# DE-180417_03.net
KiCad netlist of a schematic drawn in Altium Designer
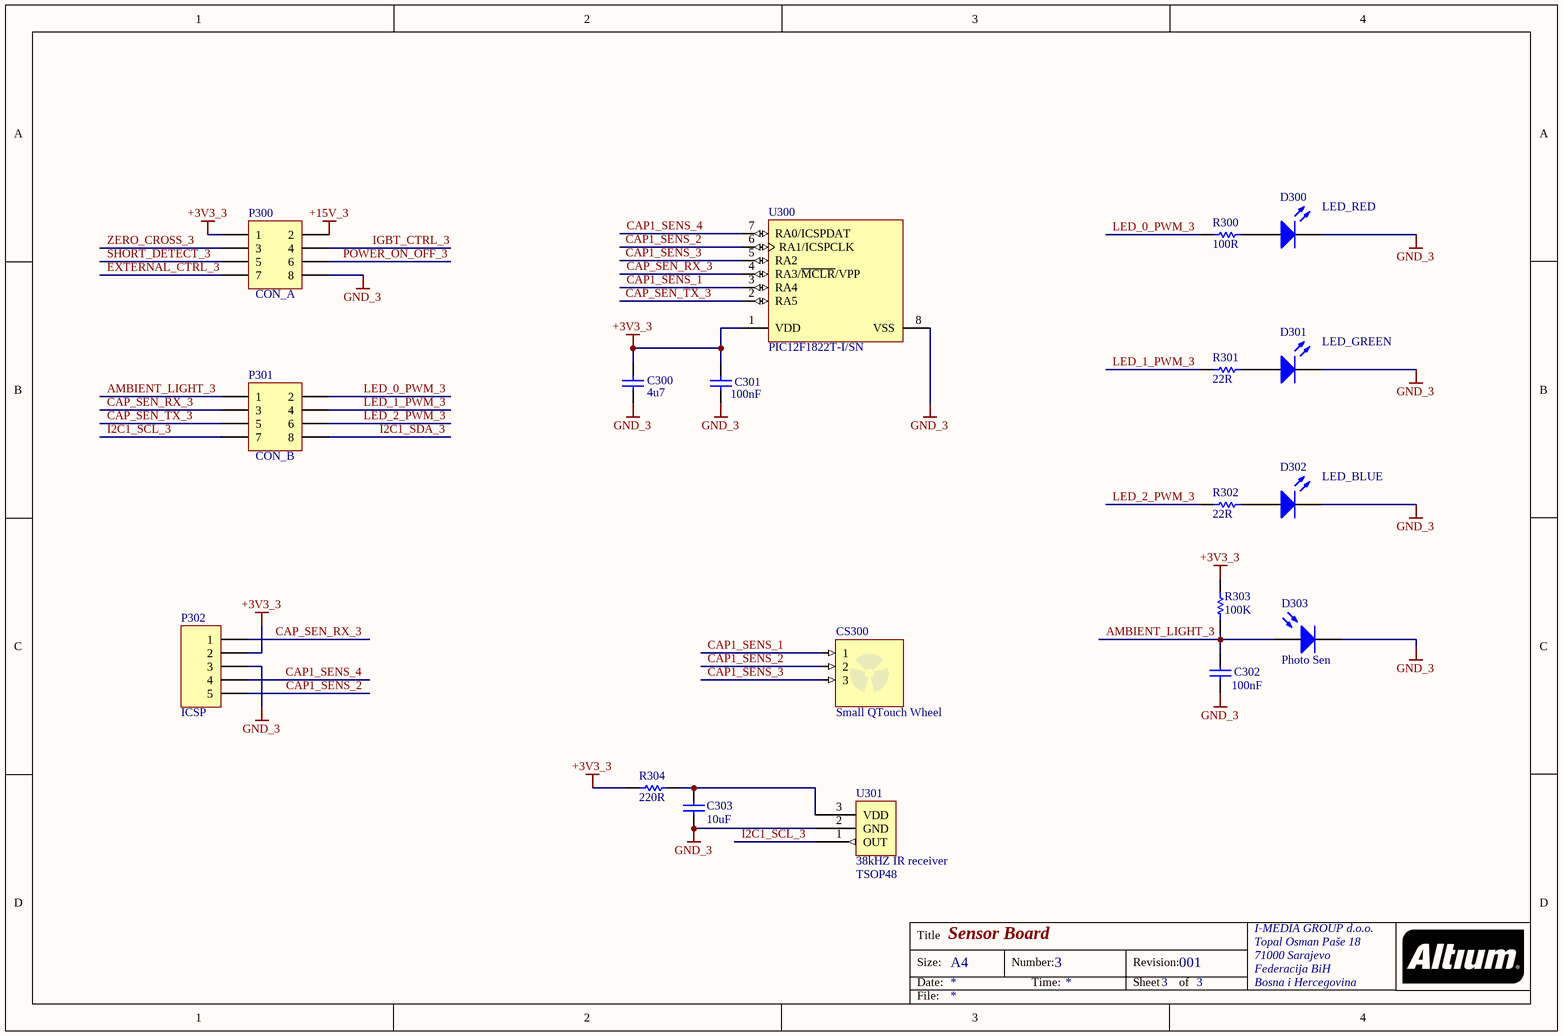
[diagram p0: DE-180417_03.SchDoc]

(export (version "E")
  (design (tool "Eeschema 10.0.6"))
  (components
    (comp (ref "C300")
      (value "4u7")
      (footprint "0805")
      (description "Ceramic Chip Capacitor - Standard")
      (fields (field (name "PUBLISHER") "Altium Limited"))
      (libsource (lib "KEMET Chip Capacitor") (part "C0805"))
    )
    (comp (ref "C301")
      (value "100nF")
      (footprint "0603")
      (description "Ceramic Chip Capacitor - Standard")
      (fields (field (name "PUBLISHER") "Altium Limited"))
      (libsource (lib "KEMET Chip Capacitor") (part "C0603"))
    )
    (comp (ref "C302")
      (value "100nF")
      (footprint "0603")
      (description "Ceramic Chip Capacitor - Standard")
      (fields (field (name "PUBLISHER") "Altium Limited"))
      (libsource (lib "KEMET Chip Capacitor") (part "C0603"))
    )
    (comp (ref "C303")
      (value "10uF")
      (footprint "0805")
      (description "Ceramic Chip Capacitor - Standard")
      (fields (field (name "PUBLISHER") "Altium Limited"))
      (libsource (lib "DE-180417") (part "C0805"))
    )
    (comp (ref "CS300")
      (value "Small QTouch Wheel")
      (libsource (lib "Atmel QTouch") (part "SmallQTouchWheel"))
    )
    (comp (ref "D300")
      (value "LED_RED")
      (footprint "1.6X0.8X0.8")
      (description "High Performance Chip LED, Red")
      (fields (field (name "PUBLISHER") "Altium Limited"))
      (libsource (lib "DE-180417") (part "HSMZ-C190"))
    )
    (comp (ref "D301")
      (value "LED_GREEN")
      (footprint "1.6X0.8X0.8")
      (description "High Performance Chip LED, Red")
      (fields (field (name "PUBLISHER") "Altium Limited"))
      (libsource (lib "DE-180417") (part "HSMZ-C190"))
    )
    (comp (ref "D302")
      (value "LED_BLUE")
      (footprint "1.6X0.8X0.8")
      (description "High Performance Chip LED, Red")
      (fields (field (name "PUBLISHER") "Altium Limited"))
      (libsource (lib "DE-180417") (part "HSMZ-C190"))
    )
    (comp (ref "D303")
      (value "Photo Sen")
      (footprint "PIN2")
      (description "Photosensitive Diode")
      (fields (field (name "PUBLISHER") "Altium Limited"))
      (libsource (lib "Miscellaneous Devices") (part "Photo Sen"))
    )
    (comp (ref "P300")
      (value "CON_A")
      (footprint "HDR2X4")
      (description "Header, 4-Pin, Dual row")
      (fields (field (name "PUBLISHER") "Altium Limited"))
      (libsource (lib "Miscellaneous Connectors") (part "Header 4X2"))
    )
    (comp (ref "P301")
      (value "CON_B")
      (footprint "HDR2X4")
      (description "Header, 4-Pin, Dual row")
      (fields (field (name "PUBLISHER") "Altium Limited"))
      (libsource (lib "Miscellaneous Connectors") (part "Header 4X2"))
    )
    (comp (ref "P302")
      (value "ICSP")
      (footprint "HDR1X5")
      (description "Header, 5-Pin")
      (fields (field (name "PUBLISHER") "Altium Limited"))
      (libsource (lib "Miscellaneous Connectors") (part "Header 5"))
    )
    (comp (ref "R300")
      (value "100R")
      (footprint "ERA-0603")
      (fields (field (name "PUBLISHER") "Altium Limited"))
      (libsource (lib "DE-180417") (part "ERAV"))
    )
    (comp (ref "R301")
      (value "22R")
      (footprint "ERA-0603")
      (fields (field (name "PUBLISHER") "Altium Limited"))
      (libsource (lib "DE-180417") (part "ERAV"))
    )
    (comp (ref "R302")
      (value "22R")
      (footprint "ERA-0603")
      (fields (field (name "PUBLISHER") "Altium Limited"))
      (libsource (lib "DE-180417") (part "ERAV"))
    )
    (comp (ref "R303")
      (value "100K")
      (footprint "ERA-0603")
      (fields (field (name "PUBLISHER") "Altium Limited"))
      (libsource (lib "DE-180417") (part "ERAV"))
    )
    (comp (ref "R304")
      (value "220R")
      (footprint "ERA-0603")
      (fields (field (name "PUBLISHER") "Altium Limited"))
      (libsource (lib "DE-180417") (part "ERAV"))
    )
    (comp (ref "U300")
      (value "PIC12F1822T-I/SN")
      (footprint "MCHP-SOIC-SN8_N")
      (fields (field (name "MANUFACTURER") "Microchip"))
      (libsource (lib "Microchip PIC12") (part "PIC12F1822T-I/SN"))
    )
    (comp (ref "U301")
      (value "38kHZ IR receiver")
      (footprint "TSOP48")
      (fields (field (name "ALTIUM_VALUE") "TSOP48"))
      (libsource (lib "DE-180417") (part "TSOP48"))
    )
  )
  (nets
    (net (code "1") (name "+3V3_3") (class "Default")
      (node (ref "C300") (pin "1") (pinfunction "1_1") (pintype "passive"))
      (node (ref "C301") (pin "1") (pinfunction "1_1") (pintype "passive"))
      (node (ref "P300") (pin "1") (pinfunction "1_1") (pintype "passive"))
      (node (ref "P302") (pin "2") (pinfunction "2_2") (pintype "passive"))
      (node (ref "R303") (pin "1") (pinfunction "1_1") (pintype "passive"))
      (node (ref "R304") (pin "1") (pinfunction "1_1") (pintype "passive"))
      (node (ref "U300") (pin "1") (pinfunction "VDD_1") (pintype "power_in"))
    )
    (net (code "2") (name "+15V_3") (class "Default")
      (node (ref "P300") (pin "2") (pinfunction "2_2") (pintype "passive"))
    )
    (net (code "3") (name "/AMBIENT_LIGHT_3") (class "Default")
      (node (ref "C302") (pin "1") (pinfunction "1_1") (pintype "passive"))
      (node (ref "D303") (pin "1") (pinfunction "A_1") (pintype "passive"))
      (node (ref "P301") (pin "1") (pinfunction "1_1") (pintype "passive"))
      (node (ref "R303") (pin "2") (pinfunction "2_2") (pintype "passive"))
    )
    (net (code "4") (name "/CAP1_SENS_1") (class "Default")
      (node (ref "CS300") (pin "1") (pinfunction "1_1") (pintype "input"))
      (node (ref "U300") (pin "3") (pinfunction "RA4_3") (pintype "bidirectional"))
    )
    (net (code "5") (name "/CAP1_SENS_2") (class "Default")
      (node (ref "CS300") (pin "2") (pinfunction "2_2") (pintype "input"))
      (node (ref "P302") (pin "5") (pinfunction "5_5") (pintype "passive"))
      (node (ref "U300") (pin "6") (pinfunction "RA1/ICSPCLK_6") (pintype "bidirectional"))
    )
    (net (code "6") (name "/CAP1_SENS_3") (class "Default")
      (node (ref "CS300") (pin "3") (pinfunction "3_3") (pintype "input"))
      (node (ref "U300") (pin "5") (pinfunction "RA2_5") (pintype "bidirectional"))
    )
    (net (code "7") (name "/CAP1_SENS_4") (class "Default")
      (node (ref "P302") (pin "4") (pinfunction "4_4") (pintype "passive"))
      (node (ref "U300") (pin "7") (pinfunction "RA0/ICSPDAT_7") (pintype "bidirectional"))
    )
    (net (code "8") (name "/CAP_SEN_RX_3") (class "Default")
      (node (ref "P301") (pin "3") (pinfunction "3_3") (pintype "passive"))
      (node (ref "P302") (pin "1") (pinfunction "1_1") (pintype "passive"))
      (node (ref "U300") (pin "4") (pinfunction "RA3/~{MCLR}/VPP_4") (pintype "bidirectional"))
    )
    (net (code "9") (name "/CAP_SEN_TX_3") (class "Default")
      (node (ref "P301") (pin "5") (pinfunction "5_5") (pintype "passive"))
      (node (ref "U300") (pin "2") (pinfunction "RA5_2") (pintype "bidirectional"))
    )
    (net (code "10") (name "/EXTERNAL_CTRL_3") (class "Default")
      (node (ref "P300") (pin "7") (pinfunction "7_7") (pintype "passive"))
    )
    (net (code "11") (name "/I2C1_SCL_3") (class "Default")
      (node (ref "P301") (pin "7") (pinfunction "7_7") (pintype "passive"))
      (node (ref "U301") (pin "1") (pinfunction "OUT_1") (pintype "output"))
    )
    (net (code "12") (name "/I2C1_SDA_3") (class "Default")
      (node (ref "P301") (pin "8") (pinfunction "8_8") (pintype "passive"))
    )
    (net (code "13") (name "/IGBT_CTRL_3") (class "Default")
      (node (ref "P300") (pin "4") (pinfunction "4_4") (pintype "passive"))
    )
    (net (code "14") (name "/LED_0_PWM_3") (class "Default")
      (node (ref "P301") (pin "2") (pinfunction "2_2") (pintype "passive"))
      (node (ref "R300") (pin "2") (pinfunction "2_2") (pintype "passive"))
    )
    (net (code "15") (name "/LED_1_PWM_3") (class "Default")
      (node (ref "P301") (pin "4") (pinfunction "4_4") (pintype "passive"))
      (node (ref "R301") (pin "2") (pinfunction "2_2") (pintype "passive"))
    )
    (net (code "16") (name "/LED_2_PWM_3") (class "Default")
      (node (ref "P301") (pin "6") (pinfunction "6_6") (pintype "passive"))
      (node (ref "R302") (pin "2") (pinfunction "2_2") (pintype "passive"))
    )
    (net (code "17") (name "/POWER_ON_OFF_3") (class "Default")
      (node (ref "P300") (pin "6") (pinfunction "6_6") (pintype "passive"))
    )
    (net (code "18") (name "/SHORT_DETECT_3") (class "Default")
      (node (ref "P300") (pin "5") (pinfunction "5_5") (pintype "passive"))
    )
    (net (code "19") (name "/ZERO_CROSS_3") (class "Default")
      (node (ref "P300") (pin "3") (pinfunction "3_3") (pintype "passive"))
    )
    (net (code "20") (name "GND_3") (class "Default")
      (node (ref "C300") (pin "2") (pinfunction "2_2") (pintype "passive"))
      (node (ref "C301") (pin "2") (pinfunction "2_2") (pintype "passive"))
      (node (ref "C302") (pin "2") (pinfunction "2_2") (pintype "passive"))
      (node (ref "C303") (pin "2") (pinfunction "2_2") (pintype "passive"))
      (node (ref "D300") (pin "2") (pinfunction "K_2") (pintype "passive"))
      (node (ref "D301") (pin "2") (pinfunction "K_2") (pintype "passive"))
      (node (ref "D302") (pin "2") (pinfunction "K_2") (pintype "passive"))
      (node (ref "D303") (pin "2") (pinfunction "K_2") (pintype "passive"))
      (node (ref "P300") (pin "8") (pinfunction "8_8") (pintype "passive"))
      (node (ref "P302") (pin "3") (pinfunction "3_3") (pintype "passive"))
      (node (ref "U300") (pin "8") (pinfunction "VSS_8") (pintype "power_in"))
      (node (ref "U301") (pin "2") (pinfunction "GND_2") (pintype "power_in"))
    )
    (net (code "21") (name "Net-(D300-A)") (class "Default")
      (node (ref "D300") (pin "1") (pinfunction "A_1") (pintype "passive"))
      (node (ref "R300") (pin "1") (pinfunction "1_1") (pintype "passive"))
    )
    (net (code "22") (name "Net-(D301-A)") (class "Default")
      (node (ref "D301") (pin "1") (pinfunction "A_1") (pintype "passive"))
      (node (ref "R301") (pin "1") (pinfunction "1_1") (pintype "passive"))
    )
    (net (code "23") (name "Net-(D302-A)") (class "Default")
      (node (ref "D302") (pin "1") (pinfunction "A_1") (pintype "passive"))
      (node (ref "R302") (pin "1") (pinfunction "1_1") (pintype "passive"))
    )
    (net (code "24") (name "Net-(U301-VDD)") (class "Default")
      (node (ref "C303") (pin "1") (pinfunction "1_1") (pintype "passive"))
      (node (ref "R304") (pin "2") (pinfunction "2_2") (pintype "passive"))
      (node (ref "U301") (pin "3") (pinfunction "VDD_3") (pintype "power_in"))
    )
  )
)
